# RJ-45_Sensor_Breakout.net
KiCad netlist of a schematic drawn in EAGLE
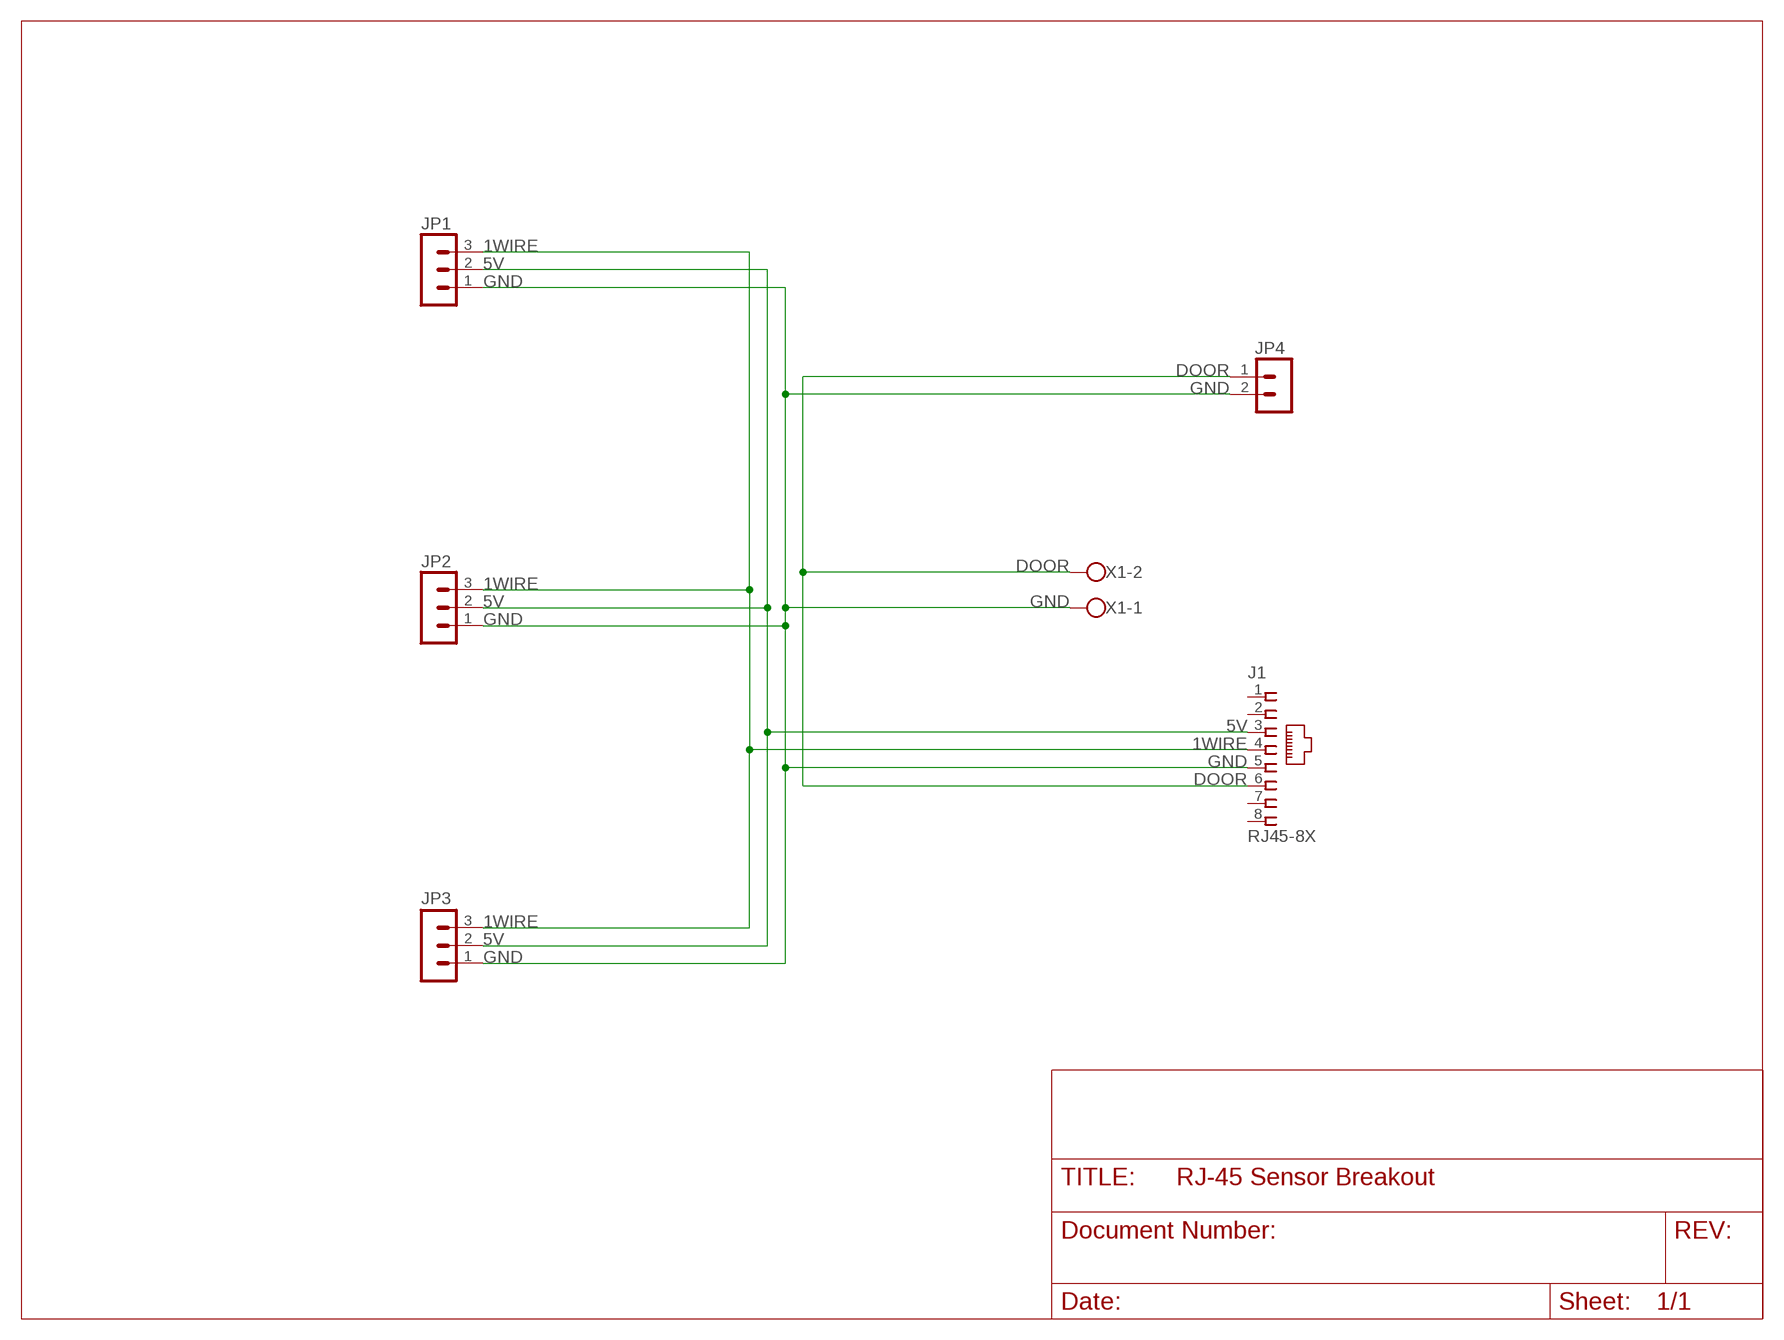
[diagram p0: schematic, sheet 1]

(export (version "E")
  (design (tool "Eeschema 10.0.6"))
  (components
    (comp (ref "J1")
      (value "RJ45-8X")
      (footprint "eagle-import:RJ45-NO-SHIELD-NOLINE")
      (libsource (lib "eagle-import") (part "RJ45-8X"))
    )
    (comp (ref "JP1")
      (value "HDR-3")
      (footprint "eagle-import:HDR-3_VERT")
      (libsource (lib "eagle-import") (part "HDR-3"))
    )
    (comp (ref "JP2")
      (value "HDR-3")
      (footprint "eagle-import:HDR-3_VERT")
      (libsource (lib "eagle-import") (part "HDR-3"))
    )
    (comp (ref "JP3")
      (value "OneWire")
      (footprint "eagle-import:HDR-3_VERT")
      (libsource (lib "eagle-import") (part "HDR-3"))
    )
    (comp (ref "JP4")
      (value "HDR-2")
      (footprint "eagle-import:HDR-2_VERT")
      (libsource (lib "eagle-import") (part "HDR-2"))
    )
    (comp (ref "X1")
      (value "W237-102")
      (footprint "eagle-import:W237-102")
      (fields (field (name "MPN") "237-102"))
      (libsource (lib "eagle-import") (part "W237-102"))
    )
  )
  (nets
    (net (code "1") (name "/1WIRE") (class "Default")
      (node (ref "J1") (pin "4") (pinfunction "4_4") (pintype "passive"))
      (node (ref "JP1") (pin "3") (pinfunction "3_3") (pintype "passive"))
      (node (ref "JP2") (pin "3") (pinfunction "3_3") (pintype "passive"))
      (node (ref "JP3") (pin "3") (pinfunction "3_3") (pintype "passive"))
    )
    (net (code "2") (name "/5V") (class "Default")
      (node (ref "J1") (pin "3") (pinfunction "3_3") (pintype "passive"))
      (node (ref "JP1") (pin "2") (pinfunction "2_2") (pintype "passive"))
      (node (ref "JP2") (pin "2") (pinfunction "2_2") (pintype "passive"))
      (node (ref "JP3") (pin "2") (pinfunction "2_2") (pintype "passive"))
    )
    (net (code "3") (name "/DOOR") (class "Default")
      (node (ref "J1") (pin "6") (pinfunction "6_6") (pintype "passive"))
      (node (ref "JP4") (pin "1") (pinfunction "1_1") (pintype "passive"))
      (node (ref "X1") (pin "2") (pinfunction "KL_2") (pintype "passive"))
    )
    (net (code "4") (name "/GND") (class "Default")
      (node (ref "J1") (pin "5") (pinfunction "5_5") (pintype "passive"))
      (node (ref "JP1") (pin "1") (pinfunction "1_1") (pintype "passive"))
      (node (ref "JP2") (pin "1") (pinfunction "1_1") (pintype "passive"))
      (node (ref "JP3") (pin "1") (pinfunction "1_1") (pintype "passive"))
      (node (ref "JP4") (pin "2") (pinfunction "2_2") (pintype "passive"))
      (node (ref "X1") (pin "1") (pinfunction "KL_1") (pintype "passive"))
    )
    (net (code "5") (name "unconnected-(J1-Pad1)") (class "Default")
      (node (ref "J1") (pin "1") (pinfunction "1_1") (pintype "passive"))
    )
    (net (code "6") (name "unconnected-(J1-Pad2)") (class "Default")
      (node (ref "J1") (pin "2") (pinfunction "2_2") (pintype "passive"))
    )
    (net (code "7") (name "unconnected-(J1-Pad7)") (class "Default")
      (node (ref "J1") (pin "7") (pinfunction "7_7") (pintype "passive"))
    )
    (net (code "8") (name "unconnected-(J1-Pad8)") (class "Default")
      (node (ref "J1") (pin "8") (pinfunction "8_8") (pintype "passive"))
    )
  )
)
